# Relay_Shield.net
KiCad netlist of a schematic drawn in EAGLE
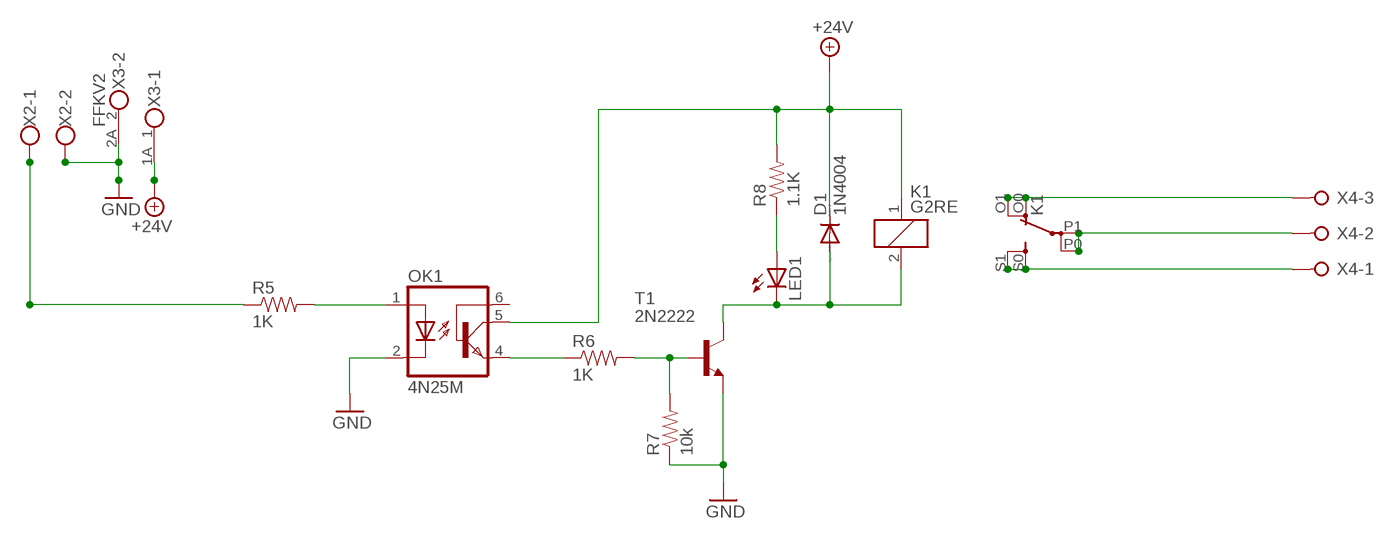
[diagram p0: schematic, sheet 1]

(export (version "E")
  (design (tool "Eeschema 10.0.6"))
  (components
    (comp (ref "D1")
      (value "1N4004")
      (footprint "eagle-import:DO41-10")
      (libsource (lib "eagle-import") (part "1N4004"))
    )
    (comp (ref "K1")
      (value "G2RE")
      (footprint "eagle-import:G2RE")
      (libsource (lib "eagle-import") (part "G2RE"))
    )
    (comp (ref "LED1")
      (value "LED3MM")
      (footprint "eagle-import:LED3MM")
      (libsource (lib "eagle-import") (part "LED3MM"))
    )
    (comp (ref "OK1")
      (value "4N25M")
      (footprint "eagle-import:DIL06")
      (fields (field (name "MPN") "4N25-M"))
      (libsource (lib "eagle-import") (part "4N?M25"))
    )
    (comp (ref "R5")
      (value "1K")
      (footprint "eagle-import:1206")
      (libsource (lib "eagle-import") (part "RESISTOR1206"))
    )
    (comp (ref "R6")
      (value "1K")
      (footprint "eagle-import:1206")
      (libsource (lib "eagle-import") (part "RESISTOR1206"))
    )
    (comp (ref "R7")
      (value "10k")
      (footprint "eagle-import:1206")
      (libsource (lib "eagle-import") (part "RESISTOR1206"))
    )
    (comp (ref "R8")
      (value "1.1K")
      (footprint "eagle-import:1206")
      (libsource (lib "eagle-import") (part "RESISTOR1206"))
    )
    (comp (ref "T1")
      (value "2N2222")
      (footprint "eagle-import:TO18")
      (libsource (lib "eagle-import") (part "2N2222"))
    )
    (comp (ref "X2")
      (value "W237-102")
      (footprint "eagle-import:W237-102")
      (fields (field (name "MPN") "237-102"))
      (libsource (lib "eagle-import") (part "W237-102"))
    )
    (comp (ref "X3")
      (value "FFKV2")
      (footprint "eagle-import:FFKV2")
      (libsource (lib "eagle-import") (part "FFKV2"))
    )
    (comp (ref "X4")
      (value "W237-3E")
      (footprint "eagle-import:W237-3E")
      (libsource (lib "eagle-import") (part "W237-3E"))
    )
  )
  (nets
    (net (code "1") (name "+24V") (class "Default")
      (node (ref "D1") (pin "C") (pinfunction "C_C") (pintype "passive"))
      (node (ref "K1") (pin "1") (pinfunction "1_1") (pintype "passive"))
      (node (ref "OK1") (pin "5") (pinfunction "COL_5") (pintype "passive"))
      (node (ref "R8") (pin "2") (pinfunction "2_2") (pintype "passive"))
      (node (ref "X3") (pin "1A") (pinfunction "2_1A") (pintype "passive"))
    )
    (net (code "2") (name "GND") (class "Default")
      (node (ref "OK1") (pin "2") (pinfunction "C_2") (pintype "passive"))
      (node (ref "R7") (pin "1") (pinfunction "1_1") (pintype "passive"))
      (node (ref "T1") (pin "1") (pinfunction "E_1") (pintype "passive"))
      (node (ref "X2") (pin "2") (pinfunction "KL_2") (pintype "passive"))
      (node (ref "X3") (pin "2A") (pinfunction "2_2A") (pintype "passive"))
    )
    (net (code "3") (name "Net-(LED1-C)") (class "Default")
      (node (ref "D1") (pin "A") (pinfunction "A_A") (pintype "passive"))
      (node (ref "K1") (pin "2") (pinfunction "2_2") (pintype "passive"))
      (node (ref "LED1") (pin "K") (pinfunction "C_K") (pintype "passive"))
      (node (ref "T1") (pin "3") (pinfunction "C_3") (pintype "passive"))
    )
    (net (code "4") (name "Net-(LED1-PadA)") (class "Default")
      (node (ref "LED1") (pin "A") (pinfunction "A_A") (pintype "passive"))
      (node (ref "R8") (pin "1") (pinfunction "1_1") (pintype "passive"))
    )
    (net (code "5") (name "Net-(OK1-A)") (class "Default")
      (node (ref "OK1") (pin "1") (pinfunction "A_1") (pintype "passive"))
      (node (ref "R5") (pin "2") (pinfunction "2_2") (pintype "passive"))
    )
    (net (code "6") (name "Net-(OK1-EMI)") (class "Default")
      (node (ref "OK1") (pin "4") (pinfunction "EMI_4") (pintype "passive"))
      (node (ref "R6") (pin "1") (pinfunction "1_1") (pintype "passive"))
    )
    (net (code "7") (name "Net-(T1-B)") (class "Default")
      (node (ref "R6") (pin "2") (pinfunction "2_2") (pintype "passive"))
      (node (ref "R7") (pin "2") (pinfunction "2_2") (pintype "passive"))
      (node (ref "T1") (pin "2") (pinfunction "B_2") (pintype "passive"))
    )
    (net (code "8") (name "Net-(X2A-KL)") (class "Default")
      (node (ref "R5") (pin "1") (pinfunction "1_1") (pintype "passive"))
      (node (ref "X2") (pin "1") (pinfunction "KL_1") (pintype "passive"))
    )
    (net (code "9") (name "Net-(X4A-KL)") (class "Default")
      (node (ref "K1") (pin "S0") (pinfunction "S_S0") (pintype "passive"))
      (node (ref "K1") (pin "S1") (pinfunction "S_S1") (pintype "passive"))
      (node (ref "X4") (pin "1") (pinfunction "KL_1") (pintype "passive"))
    )
    (net (code "10") (name "Net-(X4B-KL)") (class "Default")
      (node (ref "K1") (pin "P0") (pinfunction "P_P0") (pintype "passive"))
      (node (ref "K1") (pin "P1") (pinfunction "P_P1") (pintype "passive"))
      (node (ref "X4") (pin "2") (pinfunction "KL_2") (pintype "passive"))
    )
    (net (code "11") (name "Net-(X4C-KL)") (class "Default")
      (node (ref "K1") (pin "O0") (pinfunction "O_O0") (pintype "passive"))
      (node (ref "K1") (pin "O1") (pinfunction "O_O1") (pintype "passive"))
      (node (ref "X4") (pin "3") (pinfunction "KL_3") (pintype "passive"))
    )
    (net (code "12") (name "unconnected-(OK1-BAS-Pad6)") (class "Default")
      (node (ref "OK1") (pin "6") (pinfunction "BAS_6") (pintype "passive"))
    )
    (net (code "13") (name "unconnected-(X3-Pad1)") (class "Default")
      (node (ref "X3") (pin "1") (pinfunction "1_1") (pintype "passive"))
    )
    (net (code "14") (name "unconnected-(X3B-1-Pad2)") (class "Default")
      (node (ref "X3") (pin "2") (pinfunction "1_2") (pintype "passive"))
    )
  )
)
